# Water_Counter_Nathan_Amir.net
KiCad netlist of a schematic drawn in EasyEDA
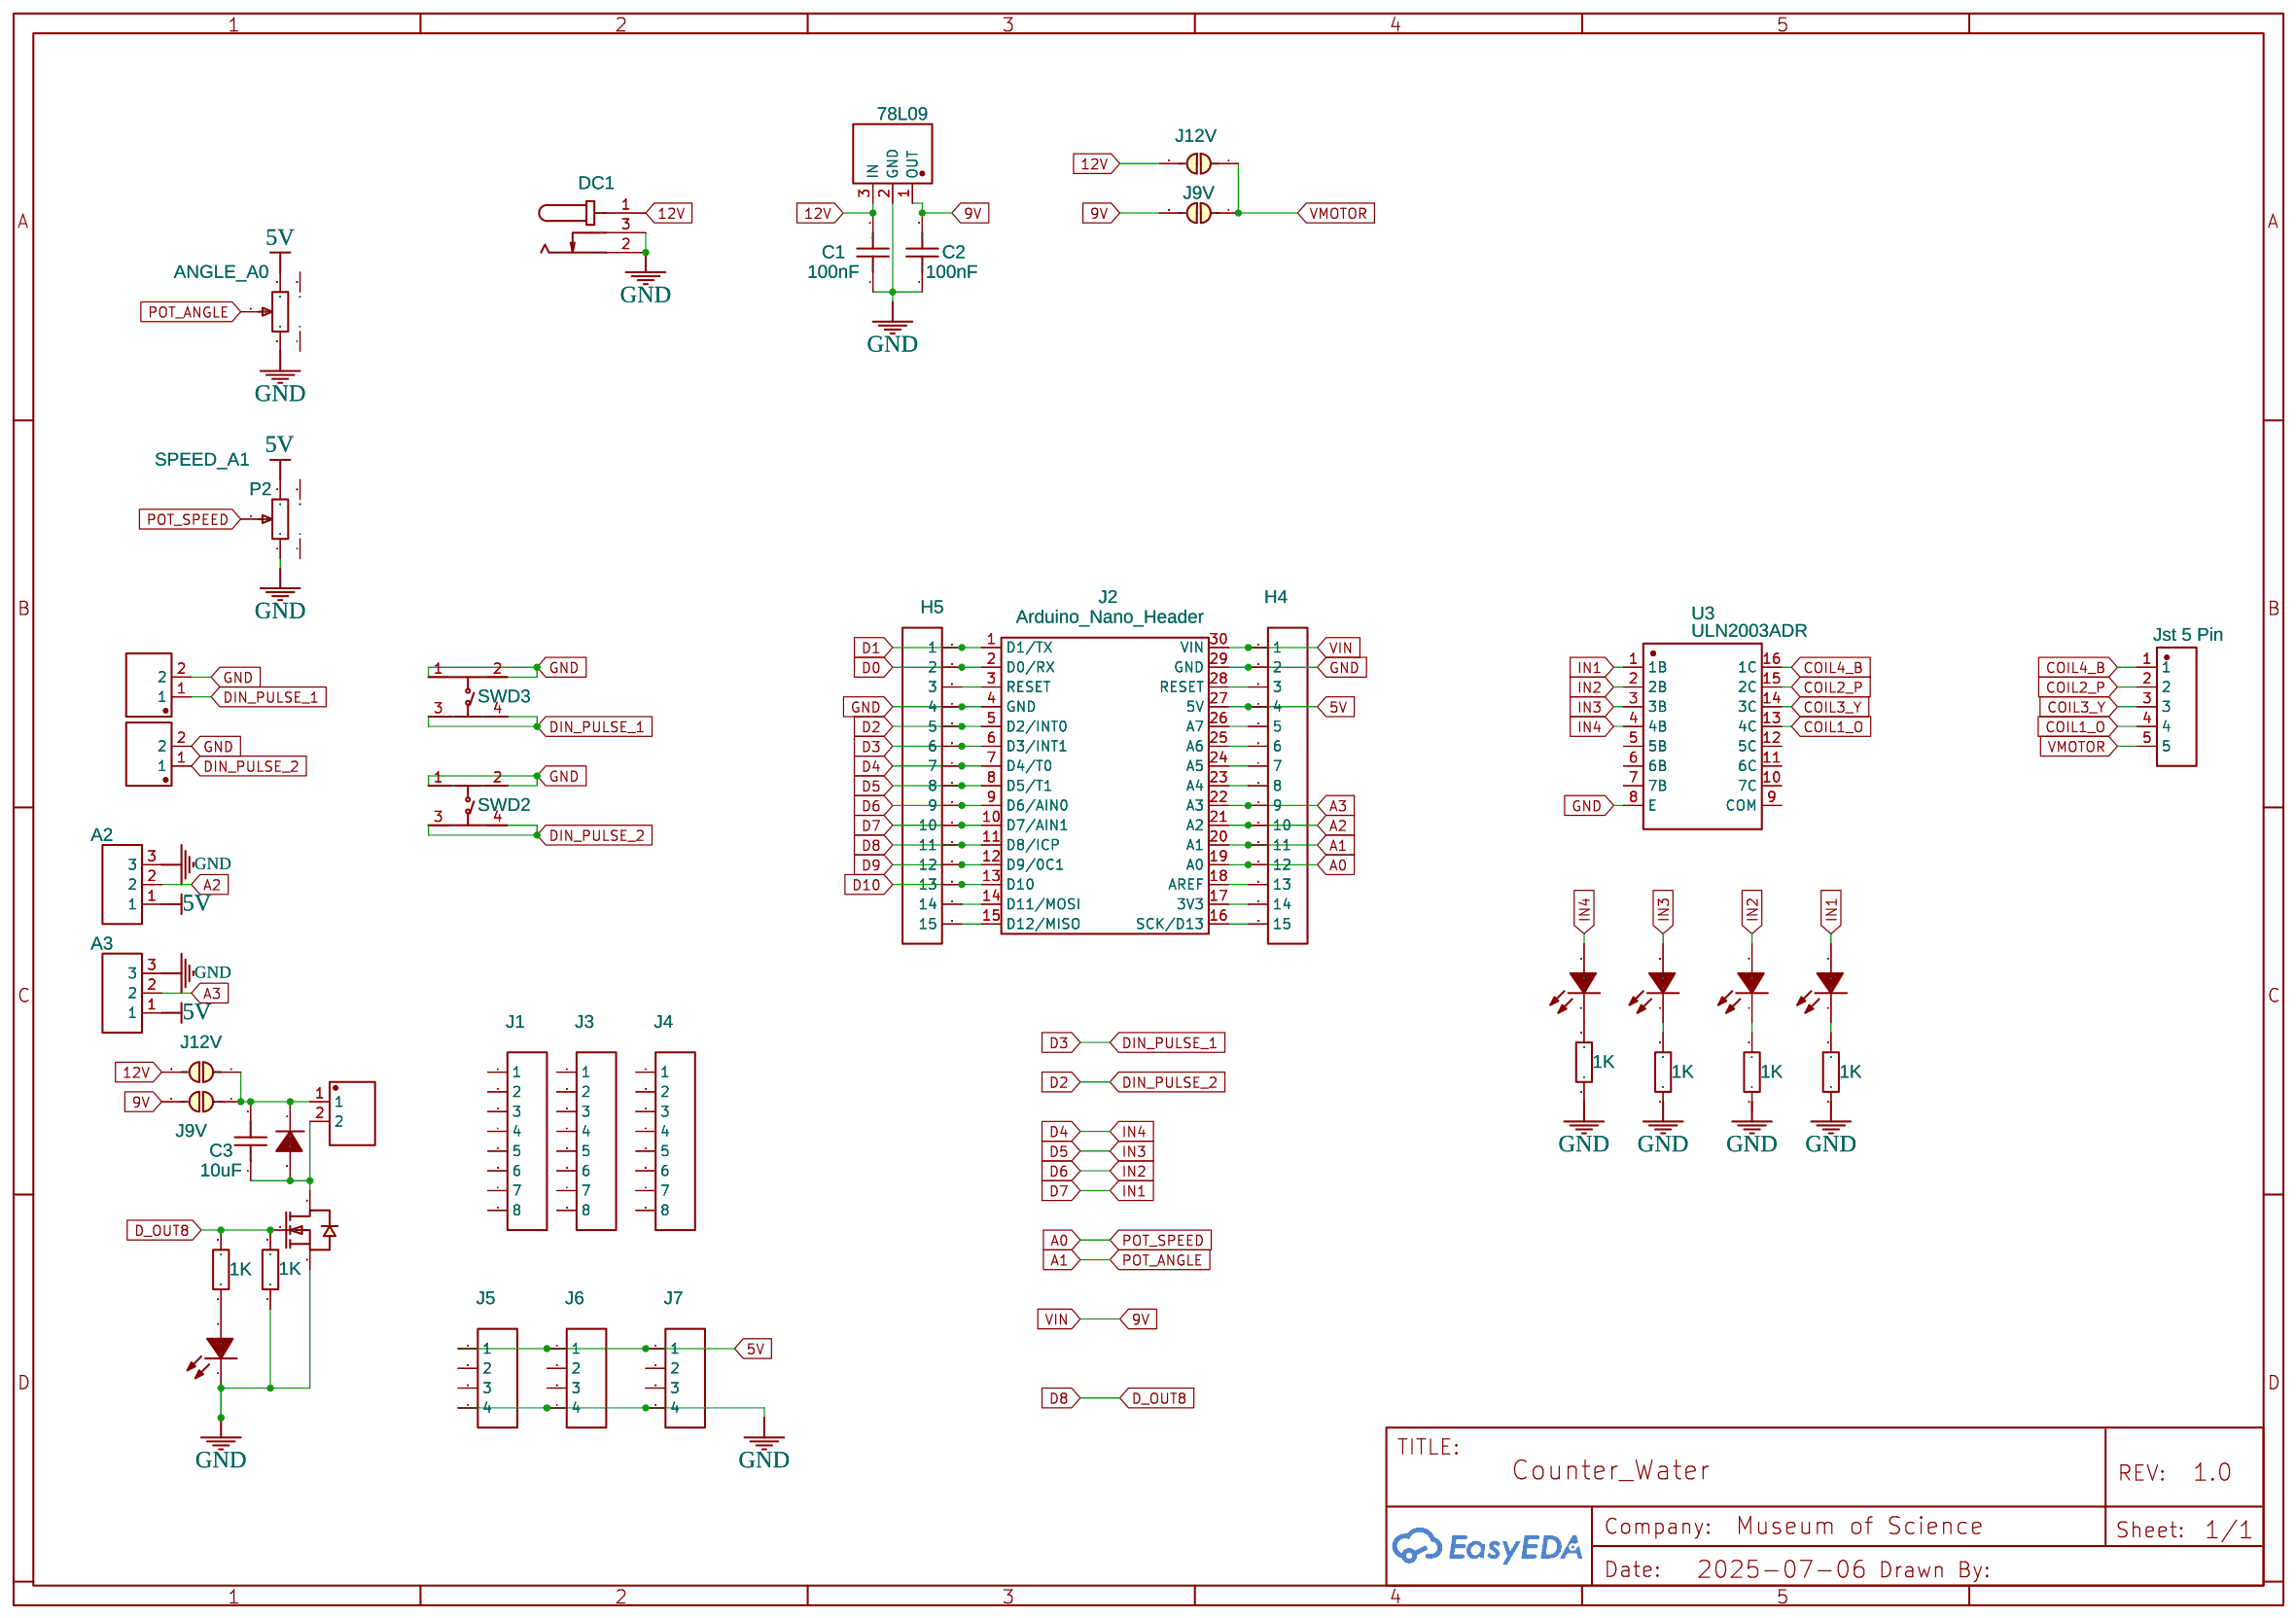
[diagram p0: schematic sheet]

(export (version "E")
  (design (tool "Eeschema 10.0.6"))
  (components
    (comp (ref "A2") (value "FK2510") (libsource (lib "") (part "kf2510_3A")))
    (comp (ref "A3") (value "FK2510") (libsource (lib "") (part "kf2510_3A")))
    (comp (ref "C1")
      (value "100nF")
      (fields
        (field (name "Manufacturer Part") "CC0603KRX7R9BB104")
        (field (name "Manufacturer") "YAGEO(国巨)")
      )
      (libsource (lib "") (part "CC0603KRX7R9BB104"))
    )
    (comp (ref "C2")
      (value "100nF")
      (fields
        (field (name "Manufacturer Part") "CC0603KRX7R9BB104")
        (field (name "Manufacturer") "YAGEO(国巨)")
      )
      (libsource (lib "") (part "CC0603KRX7R9BB104"))
    )
    (comp (ref "C3")
      (value "10uF")
      (fields
        (field (name "Manufacturer Part") "GRM21BR61H106KE43L")
        (field (name "Manufacturer") "muRata(村田)")
      )
      (libsource (lib "") (part "GRM21BR61H106KE43L"))
    )
    (comp (ref "D2")
      (value "KF2510-2A")
      (fields (field (name "Manufacturer") "BOOMELE"))
      (libsource (lib "") (part "KF2510-2A"))
    )
    (comp (ref "D3")
      (value "KF2510-2A")
      (fields (field (name "Manufacturer") "BOOMELE"))
      (libsource (lib "") (part "KF2510-2A"))
    )
    (comp (ref "DC1")
      (value "DC")
      (fields (field (name "Manufacturer Part") "DC005-2.0MM") (field (name "Manufacturer") "SOFNG"))
      (libsource (lib "") (part "DC005-2.0MM"))
    )
    (comp (ref "ECON1")
      (value "D_OUT8")
      (fields (field (name "Manufacturer Part") "KF2510-2A") (field (name "Manufacturer") "BOOMELE"))
      (libsource (lib "") (part "KF2510-2A_1"))
    )
    (comp (ref "EDM1")
      (value "1N4007")
      (fields (field (name "Manufacturer Part") "1N4007F") (field (name "Manufacturer") "SK"))
      (libsource (lib "") (part "1N4007F"))
    )
    (comp (ref "EQ1")
      (value "Q")
      (fields (field (name "Manufacturer Part") "AO3400") (field (name "Manufacturer") "ElecSuper(静芯微）"))
      (libsource (lib "") (part "JSM2302"))
    )
    (comp (ref "ERG1")
      (value "1K")
      (fields (field (name "Manufacturer Part") "0603WAF1001T5E") (field (name "Manufacturer") "UniOhm"))
      (libsource (lib "") (part "0603WAF1001T5E_1"))
    )
    (comp (ref "ERL1")
      (value "1K")
      (fields (field (name "Manufacturer Part") "0603WAF1001T5E") (field (name "Manufacturer") "UniOhm"))
      (libsource (lib "") (part "0603WAF1001T5E"))
    )
    (comp (ref "ERL2")
      (value "1K")
      (fields (field (name "Manufacturer Part") "0603WAF1001T5E") (field (name "Manufacturer") "UniOhm"))
      (libsource (lib "") (part "0603WAF1001T5E"))
    )
    (comp (ref "ERL3")
      (value "1K")
      (fields (field (name "Manufacturer Part") "0603WAF1001T5E") (field (name "Manufacturer") "UniOhm"))
      (libsource (lib "") (part "0603WAF1001T5E"))
    )
    (comp (ref "ERL4")
      (value "1K")
      (fields (field (name "Manufacturer Part") "0603WAF1001T5E") (field (name "Manufacturer") "UniOhm"))
      (libsource (lib "") (part "0603WAF1001T5E"))
    )
    (comp (ref "ERL5")
      (value "1K")
      (fields (field (name "Manufacturer Part") "0603WAF1001T5E") (field (name "Manufacturer") "UniOhm"))
      (libsource (lib "") (part "0603WAF1001T5E"))
    )
    (comp (ref "H4") (value "HDR-F-2.54_1x15") (libsource (lib "") (part "HDR-F-2.54_1x15")))
    (comp (ref "H5") (value "HDR-F-2.54_1x15") (libsource (lib "") (part "HDR-F-2.54_1x15_1")))
    (comp (ref "J1") (value "HDR-M-2.54_1x8") (libsource (lib "") (part "HDR-M-2.54_1x8")))
    (comp (ref "J2") (value "Arduino_Nano_Header") (libsource (lib "") (part "Arduino_Nano_Header")))
    (comp (ref "J3") (value "HDR-M-2.54_1x8") (libsource (lib "") (part "HDR-M-2.54_1x8")))
    (comp (ref "J4") (value "HDR-M-2.54_1x8") (libsource (lib "") (part "HDR-M-2.54_1x8")))
    (comp (ref "J5") (value "HDR-M-2.54_1x4") (libsource (lib "") (part "HDR-M-2.54_1x4")))
    (comp (ref "J5V_2") (value "J9V") (libsource (lib "") (part "JUMPER-SMT_2_2")))
    (comp (ref "J6") (value "HDR-M-2.54_1x4") (libsource (lib "") (part "HDR-M-2.54_1x4")))
    (comp (ref "J7") (value "HDR-M-2.54_1x4") (libsource (lib "") (part "HDR-M-2.54_1x4")))
    (comp (ref "J9V_1") (value "J9V") (libsource (lib "") (part "JUMPER-SMT_2")))
    (comp (ref "J12V_1") (value "J12V") (libsource (lib "") (part "JUMPER-SMT_2_1")))
    (comp (ref "J12V_2") (value "J12V") (libsource (lib "") (part "JUMPER-SMT_2_1")))
    (comp (ref "LED1")
      (value "KT-0603R")
      (fields (field (name "Manufacturer") "KENTO"))
      (libsource (lib "") (part "KT-0603R"))
    )
    (comp (ref "LED2")
      (value "KT-0603R")
      (fields (field (name "Manufacturer") "KENTO"))
      (libsource (lib "") (part "KT-0603R"))
    )
    (comp (ref "LED3")
      (value "KT-0603R")
      (fields (field (name "Manufacturer") "KENTO"))
      (libsource (lib "") (part "KT-0603R"))
    )
    (comp (ref "LED4")
      (value "KT-0603R")
      (fields (field (name "Manufacturer") "KENTO"))
      (libsource (lib "") (part "KT-0603R"))
    )
    (comp (ref "LED5")
      (value "KT-0603R")
      (fields (field (name "Manufacturer") "KENTO"))
      (libsource (lib "") (part "KT-0603R"))
    )
    (comp (ref "P2")
      (value "SPEED_A1")
      (fields (field (name "Manufacturer Part") "长柄旋转电位器"))
      (libsource (lib "") (part "长柄旋转电位器"))
    )
    (comp (ref "P3")
      (value "ANGLE_A0")
      (fields (field (name "Manufacturer Part") "长柄旋转电位器"))
      (libsource (lib "") (part "长柄旋转电位器"))
    )
    (comp (ref "SWD2")
      (value "TC-6610-7-160G")
      (fields (field (name "Manufacturer") "HCTL(华灿天禄)"))
      (libsource (lib "") (part "TC-6610-7-160G"))
    )
    (comp (ref "SWD3")
      (value "TC-6610-7-160G")
      (fields (field (name "Manufacturer") "HCTL(华灿天禄)"))
      (libsource (lib "") (part "TC-6610-7-160G"))
    )
    (comp (ref "U1")
      (value "78L09")
      (fields (field (name "Manufacturer") "CBI(创基)"))
      (libsource (lib "") (part "78L09U 78L09"))
    )
    (comp (ref "U2")
      (value "Jst 5 Pin")
      (fields (field (name "Manufacturer") "Vicky"))
      (libsource (lib "") (part "Jst 5 Pin"))
    )
    (comp (ref "U3")
      (value "ULN2003ADR")
      (fields (field (name "Manufacturer") "TI(德州仪器)"))
      (libsource (lib "") (part "ULN2003ADR"))
    )
  )
  (nets
    (net (code "1") (name "5V") (class "Default")
      (node (ref "A2") (pin "1") (pinfunction "1_1") (pintype "unspecified"))
      (node (ref "A3") (pin "1") (pinfunction "1_1") (pintype "unspecified"))
      (node (ref "H4") (pin "4") (pinfunction "4_4") (pintype "unspecified"))
      (node (ref "J2") (pin "27") (pinfunction "5V_27") (pintype "unspecified"))
      (node (ref "J5") (pin "1") (pinfunction "1_1") (pintype "unspecified"))
      (node (ref "J6") (pin "1") (pinfunction "1_1") (pintype "unspecified"))
      (node (ref "J7") (pin "1") (pinfunction "1_1") (pintype "unspecified"))
      (node (ref "P2") (pin "3") (pinfunction "3_3") (pintype "input"))
      (node (ref "P3") (pin "3") (pinfunction "3_3") (pintype "input"))
    )
    (net (code "2") (name "9V") (class "Default")
      (node (ref "C2") (pin "2") (pinfunction "2_2") (pintype "unspecified"))
      (node (ref "H4") (pin "1") (pinfunction "1_1") (pintype "unspecified"))
      (node (ref "J2") (pin "30") (pinfunction "VIN_30") (pintype "unspecified"))
      (node (ref "J5V_2") (pin "2") (pinfunction "2_2") (pintype "bidirectional"))
      (node (ref "J9V_1") (pin "2") (pinfunction "2_2") (pintype "bidirectional"))
      (node (ref "U1") (pin "1") (pinfunction "OUT_1") (pintype "unspecified"))
    )
    (net (code "3") (name "12V") (class "Default")
      (node (ref "C1") (pin "2") (pinfunction "2_2") (pintype "unspecified"))
      (node (ref "DC1") (pin "1") (pinfunction "1_1") (pintype "unspecified"))
      (node (ref "J12V_1") (pin "2") (pinfunction "2_2") (pintype "bidirectional"))
      (node (ref "J12V_2") (pin "2") (pinfunction "2_2") (pintype "bidirectional"))
      (node (ref "U1") (pin "3") (pinfunction "IN_3") (pintype "unspecified"))
    )
    (net (code "4") (name "A0") (class "Default")
      (node (ref "H4") (pin "12") (pinfunction "12_12") (pintype "unspecified"))
      (node (ref "J2") (pin "19") (pinfunction "A0_19") (pintype "unspecified"))
      (node (ref "P2") (pin "2") (pinfunction "2_2") (pintype "input"))
    )
    (net (code "5") (name "A1") (class "Default")
      (node (ref "H4") (pin "11") (pinfunction "11_11") (pintype "unspecified"))
      (node (ref "J2") (pin "20") (pinfunction "A1_20") (pintype "unspecified"))
      (node (ref "P3") (pin "2") (pinfunction "2_2") (pintype "input"))
    )
    (net (code "6") (name "A2") (class "Default")
      (node (ref "A2") (pin "2") (pinfunction "2_2") (pintype "unspecified"))
      (node (ref "H4") (pin "10") (pinfunction "10_10") (pintype "unspecified"))
      (node (ref "J2") (pin "21") (pinfunction "A2_21") (pintype "unspecified"))
    )
    (net (code "7") (name "A3") (class "Default")
      (node (ref "A3") (pin "2") (pinfunction "2_2") (pintype "unspecified"))
      (node (ref "H4") (pin "9") (pinfunction "9_9") (pintype "unspecified"))
      (node (ref "J2") (pin "22") (pinfunction "A3_22") (pintype "unspecified"))
    )
    (net (code "8") (name "COIL1_O") (class "Default")
      (node (ref "U2") (pin "4") (pinfunction "4_4") (pintype "unspecified"))
      (node (ref "U3") (pin "13") (pinfunction "4C_13") (pintype "unspecified"))
    )
    (net (code "9") (name "COIL2_P") (class "Default")
      (node (ref "U2") (pin "2") (pinfunction "2_2") (pintype "unspecified"))
      (node (ref "U3") (pin "15") (pinfunction "2C_15") (pintype "unspecified"))
    )
    (net (code "10") (name "COIL3_Y") (class "Default")
      (node (ref "U2") (pin "3") (pinfunction "3_3") (pintype "unspecified"))
      (node (ref "U3") (pin "14") (pinfunction "3C_14") (pintype "unspecified"))
    )
    (net (code "11") (name "COIL4_B") (class "Default")
      (node (ref "U2") (pin "1") (pinfunction "1_1") (pintype "unspecified"))
      (node (ref "U3") (pin "16") (pinfunction "1C_16") (pintype "unspecified"))
    )
    (net (code "12") (name "D0") (class "Default")
      (node (ref "H5") (pin "2") (pinfunction "2_2") (pintype "unspecified"))
      (node (ref "J2") (pin "2") (pinfunction "D0/RX_2") (pintype "unspecified"))
    )
    (net (code "13") (name "D1") (class "Default")
      (node (ref "H5") (pin "1") (pinfunction "1_1") (pintype "unspecified"))
      (node (ref "J2") (pin "1") (pinfunction "D1/TX_1") (pintype "unspecified"))
    )
    (net (code "14") (name "D2") (class "Default")
      (node (ref "D2") (pin "1") (pinfunction "1_1") (pintype "unspecified"))
      (node (ref "H5") (pin "5") (pinfunction "5_5") (pintype "unspecified"))
      (node (ref "J2") (pin "5") (pinfunction "D2/INT0_5") (pintype "unspecified"))
      (node (ref "SWD2") (pin "3") (pinfunction "3_3") (pintype "unspecified"))
      (node (ref "SWD2") (pin "4") (pinfunction "4_4") (pintype "unspecified"))
    )
    (net (code "15") (name "D3") (class "Default")
      (node (ref "D3") (pin "1") (pinfunction "1_1") (pintype "unspecified"))
      (node (ref "H5") (pin "6") (pinfunction "6_6") (pintype "unspecified"))
      (node (ref "J2") (pin "6") (pinfunction "D3/INT1_6") (pintype "unspecified"))
      (node (ref "SWD3") (pin "3") (pinfunction "3_3") (pintype "unspecified"))
      (node (ref "SWD3") (pin "4") (pinfunction "4_4") (pintype "unspecified"))
    )
    (net (code "16") (name "D4") (class "Default")
      (node (ref "H5") (pin "7") (pinfunction "7_7") (pintype "unspecified"))
      (node (ref "J2") (pin "7") (pinfunction "D4/T0_7") (pintype "unspecified"))
      (node (ref "LED5") (pin "2") (pinfunction "A_2") (pintype "unspecified"))
      (node (ref "U3") (pin "4") (pinfunction "4B_4") (pintype "unspecified"))
    )
    (net (code "17") (name "D5") (class "Default")
      (node (ref "H5") (pin "8") (pinfunction "8_8") (pintype "unspecified"))
      (node (ref "J2") (pin "8") (pinfunction "D5/T1_8") (pintype "unspecified"))
      (node (ref "LED4") (pin "2") (pinfunction "A_2") (pintype "unspecified"))
      (node (ref "U3") (pin "3") (pinfunction "3B_3") (pintype "unspecified"))
    )
    (net (code "18") (name "D6") (class "Default")
      (node (ref "H5") (pin "9") (pinfunction "9_9") (pintype "unspecified"))
      (node (ref "J2") (pin "9") (pinfunction "D6/AIN0_9") (pintype "unspecified"))
      (node (ref "LED3") (pin "2") (pinfunction "A_2") (pintype "unspecified"))
      (node (ref "U3") (pin "2") (pinfunction "2B_2") (pintype "unspecified"))
    )
    (net (code "19") (name "D7") (class "Default")
      (node (ref "H5") (pin "10") (pinfunction "10_10") (pintype "unspecified"))
      (node (ref "J2") (pin "10") (pinfunction "D7/AIN1_10") (pintype "unspecified"))
      (node (ref "LED2") (pin "2") (pinfunction "A_2") (pintype "unspecified"))
      (node (ref "U3") (pin "1") (pinfunction "1B_1") (pintype "unspecified"))
    )
    (net (code "20") (name "D8") (class "Default")
      (node (ref "EQ1") (pin "1") (pinfunction "G_1") (pintype "unspecified"))
      (node (ref "ERG1") (pin "2") (pinfunction "2_2") (pintype "input"))
      (node (ref "ERL5") (pin "2") (pinfunction "2_2") (pintype "input"))
      (node (ref "H5") (pin "11") (pinfunction "11_11") (pintype "unspecified"))
      (node (ref "J2") (pin "11") (pinfunction "D8/ICP_11") (pintype "unspecified"))
    )
    (net (code "21") (name "D9") (class "Default")
      (node (ref "H5") (pin "12") (pinfunction "12_12") (pintype "unspecified"))
      (node (ref "J2") (pin "12") (pinfunction "D9/0C1_12") (pintype "unspecified"))
    )
    (net (code "22") (name "D10") (class "Default")
      (node (ref "H5") (pin "13") (pinfunction "13_13") (pintype "unspecified"))
      (node (ref "J2") (pin "13") (pinfunction "D10_13") (pintype "unspecified"))
    )
    (net (code "23") (name "GND") (class "Default")
      (node (ref "A2") (pin "3") (pinfunction "3_3") (pintype "unspecified"))
      (node (ref "A3") (pin "3") (pinfunction "3_3") (pintype "unspecified"))
      (node (ref "C1") (pin "1") (pinfunction "1_1") (pintype "unspecified"))
      (node (ref "C2") (pin "1") (pinfunction "1_1") (pintype "unspecified"))
      (node (ref "D2") (pin "2") (pinfunction "2_2") (pintype "unspecified"))
      (node (ref "D3") (pin "2") (pinfunction "2_2") (pintype "unspecified"))
      (node (ref "DC1") (pin "2") (pinfunction "2_2") (pintype "unspecified"))
      (node (ref "DC1") (pin "3") (pinfunction "3_3") (pintype "unspecified"))
      (node (ref "EQ1") (pin "2") (pinfunction "S_2") (pintype "unspecified"))
      (node (ref "ERG1") (pin "1") (pinfunction "1_1") (pintype "input"))
      (node (ref "ERL1") (pin "1") (pinfunction "1_1") (pintype "input"))
      (node (ref "ERL2") (pin "1") (pinfunction "1_1") (pintype "input"))
      (node (ref "ERL3") (pin "1") (pinfunction "1_1") (pintype "input"))
      (node (ref "ERL4") (pin "1") (pinfunction "1_1") (pintype "input"))
      (node (ref "H4") (pin "2") (pinfunction "2_2") (pintype "unspecified"))
      (node (ref "H5") (pin "4") (pinfunction "4_4") (pintype "unspecified"))
      (node (ref "J2") (pin "29") (pinfunction "GND_29") (pintype "unspecified"))
      (node (ref "J2") (pin "4") (pinfunction "GND_4") (pintype "unspecified"))
      (node (ref "J5") (pin "4") (pinfunction "4_4") (pintype "unspecified"))
      (node (ref "J6") (pin "4") (pinfunction "4_4") (pintype "unspecified"))
      (node (ref "J7") (pin "4") (pinfunction "4_4") (pintype "unspecified"))
      (node (ref "LED1") (pin "1") (pinfunction "K_1") (pintype "unspecified"))
      (node (ref "P2") (pin "1") (pinfunction "1_1") (pintype "input"))
      (node (ref "P3") (pin "1") (pinfunction "1_1") (pintype "input"))
      (node (ref "SWD2") (pin "1") (pinfunction "1_1") (pintype "unspecified"))
      (node (ref "SWD2") (pin "2") (pinfunction "2_2") (pintype "unspecified"))
      (node (ref "SWD3") (pin "1") (pinfunction "1_1") (pintype "unspecified"))
      (node (ref "SWD3") (pin "2") (pinfunction "2_2") (pintype "unspecified"))
      (node (ref "U1") (pin "2") (pinfunction "GND_2") (pintype "unspecified"))
      (node (ref "U3") (pin "8") (pinfunction "E_8") (pintype "unspecified"))
    )
    (net (code "24") (name "Net-(EDM1-A)") (class "Default")
      (node (ref "C3") (pin "1") (pinfunction "1_1") (pintype "unspecified"))
      (node (ref "ECON1") (pin "2") (pinfunction "2_2") (pintype "unspecified"))
      (node (ref "EDM1") (pin "2") (pinfunction "A_2") (pintype "unspecified"))
      (node (ref "EQ1") (pin "3") (pinfunction "D_3") (pintype "unspecified"))
    )
    (net (code "25") (name "Net-(EDM1-C)") (class "Default")
      (node (ref "C3") (pin "2") (pinfunction "2_2") (pintype "unspecified"))
      (node (ref "ECON1") (pin "1") (pinfunction "1_1") (pintype "unspecified"))
      (node (ref "EDM1") (pin "1") (pinfunction "C_1") (pintype "unspecified"))
      (node (ref "J12V_2") (pin "1") (pinfunction "1_1") (pintype "bidirectional"))
      (node (ref "J5V_2") (pin "1") (pinfunction "1_1") (pintype "bidirectional"))
    )
    (net (code "26") (name "Net-(H4-Pad3)") (class "Default")
      (node (ref "H4") (pin "3") (pinfunction "3_3") (pintype "unspecified"))
      (node (ref "J2") (pin "28") (pinfunction "RESET_28") (pintype "unspecified"))
    )
    (net (code "27") (name "Net-(H5-Pad3)") (class "Default")
      (node (ref "H5") (pin "3") (pinfunction "3_3") (pintype "unspecified"))
      (node (ref "J2") (pin "3") (pinfunction "RESET_3") (pintype "unspecified"))
    )
    (net (code "28") (name "Net-(J2-3V3)") (class "Default")
      (node (ref "H4") (pin "14") (pinfunction "14_14") (pintype "unspecified"))
      (node (ref "J2") (pin "17") (pinfunction "3V3_17") (pintype "unspecified"))
    )
    (net (code "29") (name "Net-(J2-A4)") (class "Default")
      (node (ref "H4") (pin "8") (pinfunction "8_8") (pintype "unspecified"))
      (node (ref "J2") (pin "23") (pinfunction "A4_23") (pintype "unspecified"))
    )
    (net (code "30") (name "Net-(J2-A5)") (class "Default")
      (node (ref "H4") (pin "7") (pinfunction "7_7") (pintype "unspecified"))
      (node (ref "J2") (pin "24") (pinfunction "A5_24") (pintype "unspecified"))
    )
    (net (code "31") (name "Net-(J2-A6)") (class "Default")
      (node (ref "H4") (pin "6") (pinfunction "6_6") (pintype "unspecified"))
      (node (ref "J2") (pin "25") (pinfunction "A6_25") (pintype "unspecified"))
    )
    (net (code "32") (name "Net-(J2-A7)") (class "Default")
      (node (ref "H4") (pin "5") (pinfunction "5_5") (pintype "unspecified"))
      (node (ref "J2") (pin "26") (pinfunction "A7_26") (pintype "unspecified"))
    )
    (net (code "33") (name "Net-(J2-AREF)") (class "Default")
      (node (ref "H4") (pin "13") (pinfunction "13_13") (pintype "unspecified"))
      (node (ref "J2") (pin "18") (pinfunction "AREF_18") (pintype "unspecified"))
    )
    (net (code "34") (name "Net-(J2-D11{slash}MOSI)") (class "Default")
      (node (ref "H5") (pin "14") (pinfunction "14_14") (pintype "unspecified"))
      (node (ref "J2") (pin "14") (pinfunction "D11/MOSI_14") (pintype "unspecified"))
    )
    (net (code "35") (name "Net-(J2-D12{slash}MISO)") (class "Default")
      (node (ref "H5") (pin "15") (pinfunction "15_15") (pintype "unspecified"))
      (node (ref "J2") (pin "15") (pinfunction "D12/MISO_15") (pintype "unspecified"))
    )
    (net (code "36") (name "Net-(J2-SCK{slash}D13)") (class "Default")
      (node (ref "H4") (pin "15") (pinfunction "15_15") (pintype "unspecified"))
      (node (ref "J2") (pin "16") (pinfunction "SCK/D13_16") (pintype "unspecified"))
    )
    (net (code "37") (name "Net-(LED1-A)") (class "Default")
      (node (ref "ERL5") (pin "1") (pinfunction "1_1") (pintype "input"))
      (node (ref "LED1") (pin "2") (pinfunction "A_2") (pintype "unspecified"))
    )
    (net (code "38") (name "Net-(LED2-K)") (class "Default")
      (node (ref "ERL3") (pin "2") (pinfunction "2_2") (pintype "input"))
      (node (ref "LED2") (pin "1") (pinfunction "K_1") (pintype "unspecified"))
    )
    (net (code "39") (name "Net-(LED3-K)") (class "Default")
      (node (ref "ERL2") (pin "2") (pinfunction "2_2") (pintype "input"))
      (node (ref "LED3") (pin "1") (pinfunction "K_1") (pintype "unspecified"))
    )
    (net (code "40") (name "Net-(LED4-K)") (class "Default")
      (node (ref "ERL4") (pin "2") (pinfunction "2_2") (pintype "input"))
      (node (ref "LED4") (pin "1") (pinfunction "K_1") (pintype "unspecified"))
    )
    (net (code "41") (name "Net-(LED5-K)") (class "Default")
      (node (ref "ERL1") (pin "2") (pinfunction "2_2") (pintype "input"))
      (node (ref "LED5") (pin "1") (pinfunction "K_1") (pintype "unspecified"))
    )
    (net (code "42") (name "VMOTOR") (class "Default")
      (node (ref "J12V_1") (pin "1") (pinfunction "1_1") (pintype "bidirectional"))
      (node (ref "J9V_1") (pin "1") (pinfunction "1_1") (pintype "bidirectional"))
      (node (ref "U2") (pin "5") (pinfunction "5_5") (pintype "unspecified"))
    )
    (net (code "43") (name "unconnected-(J1-Pad1)") (class "Default")
      (node (ref "J1") (pin "1") (pinfunction "1_1") (pintype "unspecified"))
    )
    (net (code "44") (name "unconnected-(J1-Pad2)") (class "Default")
      (node (ref "J1") (pin "2") (pinfunction "2_2") (pintype "unspecified"))
    )
    (net (code "45") (name "unconnected-(J1-Pad3)") (class "Default")
      (node (ref "J1") (pin "3") (pinfunction "3_3") (pintype "unspecified"))
    )
    (net (code "46") (name "unconnected-(J1-Pad4)") (class "Default")
      (node (ref "J1") (pin "4") (pinfunction "4_4") (pintype "unspecified"))
    )
    (net (code "47") (name "unconnected-(J1-Pad5)") (class "Default")
      (node (ref "J1") (pin "5") (pinfunction "5_5") (pintype "unspecified"))
    )
    (net (code "48") (name "unconnected-(J1-Pad6)") (class "Default")
      (node (ref "J1") (pin "6") (pinfunction "6_6") (pintype "unspecified"))
    )
    (net (code "49") (name "unconnected-(J1-Pad7)") (class "Default")
      (node (ref "J1") (pin "7") (pinfunction "7_7") (pintype "unspecified"))
    )
    (net (code "50") (name "unconnected-(J1-Pad8)") (class "Default")
      (node (ref "J1") (pin "8") (pinfunction "8_8") (pintype "unspecified"))
    )
    (net (code "51") (name "unconnected-(J3-Pad1)") (class "Default")
      (node (ref "J3") (pin "1") (pinfunction "1_1") (pintype "unspecified"))
    )
    (net (code "52") (name "unconnected-(J3-Pad2)") (class "Default")
      (node (ref "J3") (pin "2") (pinfunction "2_2") (pintype "unspecified"))
    )
    (net (code "53") (name "unconnected-(J3-Pad3)") (class "Default")
      (node (ref "J3") (pin "3") (pinfunction "3_3") (pintype "unspecified"))
    )
    (net (code "54") (name "unconnected-(J3-Pad4)") (class "Default")
      (node (ref "J3") (pin "4") (pinfunction "4_4") (pintype "unspecified"))
    )
    (net (code "55") (name "unconnected-(J3-Pad5)") (class "Default")
      (node (ref "J3") (pin "5") (pinfunction "5_5") (pintype "unspecified"))
    )
    (net (code "56") (name "unconnected-(J3-Pad6)") (class "Default")
      (node (ref "J3") (pin "6") (pinfunction "6_6") (pintype "unspecified"))
    )
    (net (code "57") (name "unconnected-(J3-Pad7)") (class "Default")
      (node (ref "J3") (pin "7") (pinfunction "7_7") (pintype "unspecified"))
    )
    (net (code "58") (name "unconnected-(J3-Pad8)") (class "Default")
      (node (ref "J3") (pin "8") (pinfunction "8_8") (pintype "unspecified"))
    )
    (net (code "59") (name "unconnected-(J4-Pad1)") (class "Default")
      (node (ref "J4") (pin "1") (pinfunction "1_1") (pintype "unspecified"))
    )
    (net (code "60") (name "unconnected-(J4-Pad2)") (class "Default")
      (node (ref "J4") (pin "2") (pinfunction "2_2") (pintype "unspecified"))
    )
    (net (code "61") (name "unconnected-(J4-Pad3)") (class "Default")
      (node (ref "J4") (pin "3") (pinfunction "3_3") (pintype "unspecified"))
    )
    (net (code "62") (name "unconnected-(J4-Pad4)") (class "Default")
      (node (ref "J4") (pin "4") (pinfunction "4_4") (pintype "unspecified"))
    )
    (net (code "63") (name "unconnected-(J4-Pad5)") (class "Default")
      (node (ref "J4") (pin "5") (pinfunction "5_5") (pintype "unspecified"))
    )
    (net (code "64") (name "unconnected-(J4-Pad6)") (class "Default")
      (node (ref "J4") (pin "6") (pinfunction "6_6") (pintype "unspecified"))
    )
    (net (code "65") (name "unconnected-(J4-Pad7)") (class "Default")
      (node (ref "J4") (pin "7") (pinfunction "7_7") (pintype "unspecified"))
    )
    (net (code "66") (name "unconnected-(J4-Pad8)") (class "Default")
      (node (ref "J4") (pin "8") (pinfunction "8_8") (pintype "unspecified"))
    )
    (net (code "67") (name "unconnected-(J5-Pad2)") (class "Default")
      (node (ref "J5") (pin "2") (pinfunction "2_2") (pintype "unspecified"))
    )
    (net (code "68") (name "unconnected-(J5-Pad3)") (class "Default")
      (node (ref "J5") (pin "3") (pinfunction "3_3") (pintype "unspecified"))
    )
    (net (code "69") (name "unconnected-(J6-Pad2)") (class "Default")
      (node (ref "J6") (pin "2") (pinfunction "2_2") (pintype "unspecified"))
    )
    (net (code "70") (name "unconnected-(J6-Pad3)") (class "Default")
      (node (ref "J6") (pin "3") (pinfunction "3_3") (pintype "unspecified"))
    )
    (net (code "71") (name "unconnected-(J7-Pad2)") (class "Default")
      (node (ref "J7") (pin "2") (pinfunction "2_2") (pintype "unspecified"))
    )
    (net (code "72") (name "unconnected-(J7-Pad3)") (class "Default")
      (node (ref "J7") (pin "3") (pinfunction "3_3") (pintype "unspecified"))
    )
    (net (code "73") (name "unconnected-(P2-Pad4)") (class "Default")
      (node (ref "P2") (pin "4") (pinfunction "4_4") (pintype "input"))
    )
    (net (code "74") (name "unconnected-(P2-Pad5)") (class "Default")
      (node (ref "P2") (pin "5") (pinfunction "5_5") (pintype "input"))
    )
    (net (code "75") (name "unconnected-(P3-Pad4)") (class "Default")
      (node (ref "P3") (pin "4") (pinfunction "4_4") (pintype "input"))
    )
    (net (code "76") (name "unconnected-(P3-Pad5)") (class "Default")
      (node (ref "P3") (pin "5") (pinfunction "5_5") (pintype "input"))
    )
    (net (code "77") (name "unconnected-(U3-5B-Pad5)") (class "Default")
      (node (ref "U3") (pin "5") (pinfunction "5B_5") (pintype "unspecified"))
    )
    (net (code "78") (name "unconnected-(U3-5C-Pad12)") (class "Default")
      (node (ref "U3") (pin "12") (pinfunction "5C_12") (pintype "unspecified"))
    )
    (net (code "79") (name "unconnected-(U3-6B-Pad6)") (class "Default")
      (node (ref "U3") (pin "6") (pinfunction "6B_6") (pintype "unspecified"))
    )
    (net (code "80") (name "unconnected-(U3-6C-Pad11)") (class "Default")
      (node (ref "U3") (pin "11") (pinfunction "6C_11") (pintype "unspecified"))
    )
    (net (code "81") (name "unconnected-(U3-7B-Pad7)") (class "Default")
      (node (ref "U3") (pin "7") (pinfunction "7B_7") (pintype "unspecified"))
    )
    (net (code "82") (name "unconnected-(U3-7C-Pad10)") (class "Default")
      (node (ref "U3") (pin "10") (pinfunction "7C_10") (pintype "unspecified"))
    )
    (net (code "83") (name "unconnected-(U3-COM-Pad9)") (class "Default")
      (node (ref "U3") (pin "9") (pinfunction "COM_9") (pintype "unspecified"))
    )
  )
)
